# BrakeLight_Schematic.net
KiCad netlist of a schematic drawn in Altium Designer
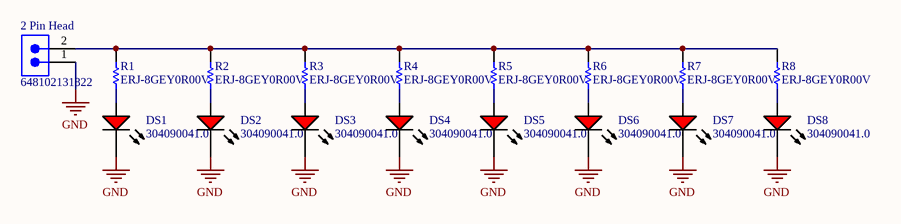
[diagram p0: BrakeLight_Schematic.SchDoc]

(export (version "E")
  (design (tool "Eeschema 10.0.6"))
  (components
    (comp (ref "2 Pin Head")
      (value "648102131822")
      (footprint "648102131822")
      (libsource (lib "Altium Content Vault") (part "Header_Male_1R_02P"))
    )
    (comp (ref "DS1")
      (value "304090041.0")
      (footprint "LED-2P-2.28-3MM_A")
      (description "Red LED, 1.9 to 2.4 V, -25 to 85 degC, 2-Pin THD")
      (fields (field (name "MANUFACTURER") "Shenzhen CGX"))
      (libsource (lib "Altium Content Vault") (part "LED-RED-AK-2"))
    )
    (comp (ref "DS2")
      (value "304090041.0")
      (footprint "LED-2P-2.28-3MM_A")
      (description "Red LED, 1.9 to 2.4 V, -25 to 85 degC, 2-Pin THD")
      (fields (field (name "MANUFACTURER") "Shenzhen CGX"))
      (libsource (lib "Altium Content Vault") (part "LED-RED-AK-2"))
    )
    (comp (ref "DS3")
      (value "304090041.0")
      (footprint "LED-2P-2.28-3MM_A")
      (description "Red LED, 1.9 to 2.4 V, -25 to 85 degC, 2-Pin THD")
      (fields (field (name "MANUFACTURER") "Shenzhen CGX"))
      (libsource (lib "Altium Content Vault") (part "LED-RED-AK-2"))
    )
    (comp (ref "DS4")
      (value "304090041.0")
      (footprint "LED-2P-2.28-3MM_A")
      (description "Red LED, 1.9 to 2.4 V, -25 to 85 degC, 2-Pin THD")
      (fields (field (name "MANUFACTURER") "Shenzhen CGX"))
      (libsource (lib "Altium Content Vault") (part "LED-RED-AK-2"))
    )
    (comp (ref "DS5")
      (value "304090041.0")
      (footprint "LED-2P-2.28-3MM_A")
      (description "Red LED, 1.9 to 2.4 V, -25 to 85 degC, 2-Pin THD")
      (fields (field (name "MANUFACTURER") "Shenzhen CGX"))
      (libsource (lib "Altium Content Vault") (part "LED-RED-AK-2"))
    )
    (comp (ref "DS6")
      (value "304090041.0")
      (footprint "LED-2P-2.28-3MM_A")
      (description "Red LED, 1.9 to 2.4 V, -25 to 85 degC, 2-Pin THD")
      (fields (field (name "MANUFACTURER") "Shenzhen CGX"))
      (libsource (lib "Altium Content Vault") (part "LED-RED-AK-2"))
    )
    (comp (ref "DS7")
      (value "304090041.0")
      (footprint "LED-2P-2.28-3MM_A")
      (description "Red LED, 1.9 to 2.4 V, -25 to 85 degC, 2-Pin THD")
      (fields (field (name "MANUFACTURER") "Shenzhen CGX"))
      (libsource (lib "Altium Content Vault") (part "LED-RED-AK-2"))
    )
    (comp (ref "DS8")
      (value "304090041.0")
      (footprint "LED-2P-2.28-3MM_A")
      (description "Red LED, 1.9 to 2.4 V, -25 to 85 degC, 2-Pin THD")
      (fields (field (name "MANUFACTURER") "Shenzhen CGX"))
      (libsource (lib "Altium Content Vault") (part "LED-RED-AK-2"))
    )
    (comp (ref "R1")
      (value "ERJ-8GEY0R00V")
      (footprint "RESC3216X70X50NL05T20")
      (fields (field (name "MANUFACTURER") "Panasonic"))
      (libsource (lib "Altium Content Vault") (part "RES"))
    )
    (comp (ref "R2")
      (value "ERJ-8GEY0R00V")
      (footprint "RESC3216X70X50NL05T20")
      (fields (field (name "MANUFACTURER") "Panasonic"))
      (libsource (lib "Altium Content Vault") (part "RES"))
    )
    (comp (ref "R3")
      (value "ERJ-8GEY0R00V")
      (footprint "RESC3216X70X50NL05T20")
      (fields (field (name "MANUFACTURER") "Panasonic"))
      (libsource (lib "Altium Content Vault") (part "RES"))
    )
    (comp (ref "R4")
      (value "ERJ-8GEY0R00V")
      (footprint "RESC3216X70X50NL05T20")
      (fields (field (name "MANUFACTURER") "Panasonic"))
      (libsource (lib "Altium Content Vault") (part "RES"))
    )
    (comp (ref "R5")
      (value "ERJ-8GEY0R00V")
      (footprint "RESC3216X70X50NL05T20")
      (fields (field (name "MANUFACTURER") "Panasonic"))
      (libsource (lib "Altium Content Vault") (part "RES"))
    )
    (comp (ref "R6")
      (value "ERJ-8GEY0R00V")
      (footprint "RESC3216X70X50NL05T20")
      (fields (field (name "MANUFACTURER") "Panasonic"))
      (libsource (lib "Altium Content Vault") (part "RES"))
    )
    (comp (ref "R7")
      (value "ERJ-8GEY0R00V")
      (footprint "RESC3216X70X50NL05T20")
      (fields (field (name "MANUFACTURER") "Panasonic"))
      (libsource (lib "Altium Content Vault") (part "RES"))
    )
    (comp (ref "R8")
      (value "ERJ-8GEY0R00V")
      (footprint "RESC3216X70X50NL05T20")
      (fields (field (name "MANUFACTURER") "Panasonic"))
      (libsource (lib "Altium Content Vault") (part "RES"))
    )
  )
  (nets
    (net (code "1") (name "GND") (class "Default")
      (node (ref "2 Pin Head") (pin "1") (pinfunction "1_1") (pintype "passive"))
      (node (ref "DS1") (pin "2") (pinfunction "K_2") (pintype "passive"))
      (node (ref "DS2") (pin "2") (pinfunction "K_2") (pintype "passive"))
      (node (ref "DS3") (pin "2") (pinfunction "K_2") (pintype "passive"))
      (node (ref "DS4") (pin "2") (pinfunction "K_2") (pintype "passive"))
      (node (ref "DS5") (pin "2") (pinfunction "K_2") (pintype "passive"))
      (node (ref "DS6") (pin "2") (pinfunction "K_2") (pintype "passive"))
      (node (ref "DS7") (pin "2") (pinfunction "K_2") (pintype "passive"))
      (node (ref "DS8") (pin "2") (pinfunction "K_2") (pintype "passive"))
    )
    (net (code "2") (name "Net-(2 Pin Head-Pad2)") (class "Default")
      (node (ref "2 Pin Head") (pin "2") (pinfunction "2_2") (pintype "passive"))
      (node (ref "R1") (pin "2") (pinfunction "2_2") (pintype "passive"))
      (node (ref "R2") (pin "2") (pinfunction "2_2") (pintype "passive"))
      (node (ref "R3") (pin "2") (pinfunction "2_2") (pintype "passive"))
      (node (ref "R4") (pin "2") (pinfunction "2_2") (pintype "passive"))
      (node (ref "R5") (pin "2") (pinfunction "2_2") (pintype "passive"))
      (node (ref "R6") (pin "2") (pinfunction "2_2") (pintype "passive"))
      (node (ref "R7") (pin "2") (pinfunction "2_2") (pintype "passive"))
      (node (ref "R8") (pin "2") (pinfunction "2_2") (pintype "passive"))
    )
    (net (code "3") (name "Net-(DS1-A)") (class "Default")
      (node (ref "DS1") (pin "1") (pinfunction "A_1") (pintype "passive"))
      (node (ref "R1") (pin "1") (pinfunction "1_1") (pintype "passive"))
    )
    (net (code "4") (name "Net-(DS2-A)") (class "Default")
      (node (ref "DS2") (pin "1") (pinfunction "A_1") (pintype "passive"))
      (node (ref "R2") (pin "1") (pinfunction "1_1") (pintype "passive"))
    )
    (net (code "5") (name "Net-(DS3-A)") (class "Default")
      (node (ref "DS3") (pin "1") (pinfunction "A_1") (pintype "passive"))
      (node (ref "R3") (pin "1") (pinfunction "1_1") (pintype "passive"))
    )
    (net (code "6") (name "Net-(DS4-A)") (class "Default")
      (node (ref "DS4") (pin "1") (pinfunction "A_1") (pintype "passive"))
      (node (ref "R4") (pin "1") (pinfunction "1_1") (pintype "passive"))
    )
    (net (code "7") (name "Net-(DS5-A)") (class "Default")
      (node (ref "DS5") (pin "1") (pinfunction "A_1") (pintype "passive"))
      (node (ref "R5") (pin "1") (pinfunction "1_1") (pintype "passive"))
    )
    (net (code "8") (name "Net-(DS6-A)") (class "Default")
      (node (ref "DS6") (pin "1") (pinfunction "A_1") (pintype "passive"))
      (node (ref "R6") (pin "1") (pinfunction "1_1") (pintype "passive"))
    )
    (net (code "9") (name "Net-(DS7-A)") (class "Default")
      (node (ref "DS7") (pin "1") (pinfunction "A_1") (pintype "passive"))
      (node (ref "R7") (pin "1") (pinfunction "1_1") (pintype "passive"))
    )
    (net (code "10") (name "Net-(DS8-A)") (class "Default")
      (node (ref "DS8") (pin "1") (pinfunction "A_1") (pintype "passive"))
      (node (ref "R8") (pin "1") (pinfunction "1_1") (pintype "passive"))
    )
  )
)
